# 19_EMMC_FLASH.net
KiCad netlist of a schematic drawn in Altium Designer
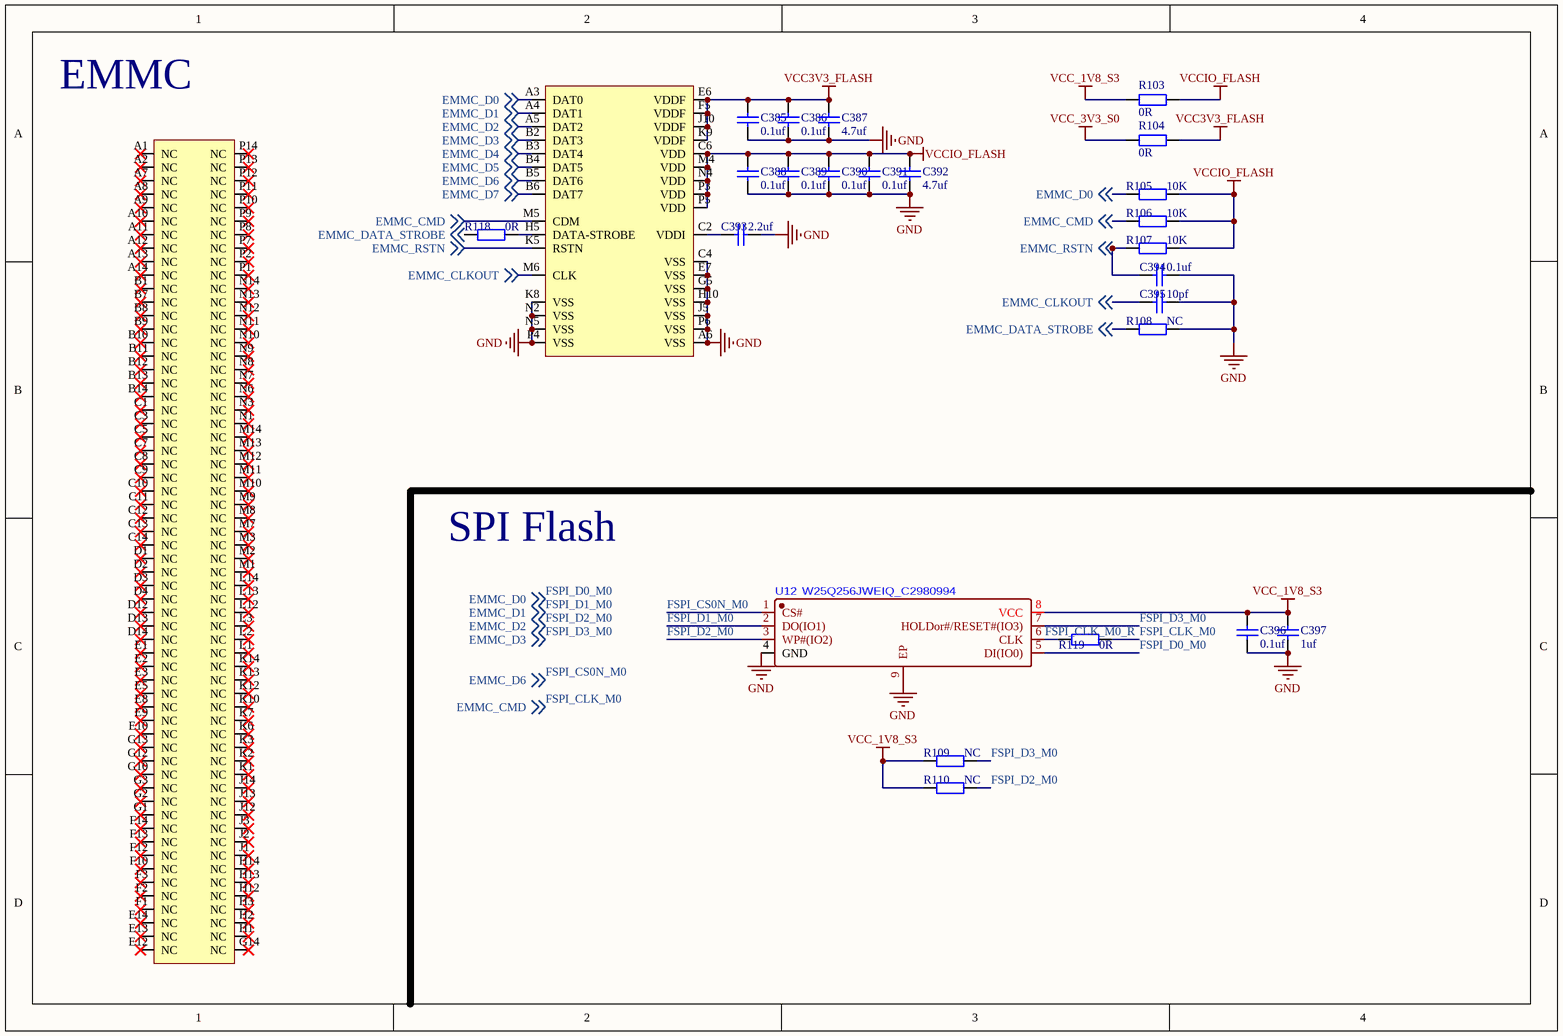
[diagram p0: 19.EMMC_FLASH.SchDoc]

(export (version "E")
  (design (tool "Eeschema 10.0.6"))
  (components
    (comp (ref "C385")
      (value "0.1uf")
      (footprint "0.PCB1:C0402_L")
      (description "贴片电容/MLCC电容")
      (libsource (lib "RK3588") (part "C"))
    )
    (comp (ref "C386")
      (value "0.1uf")
      (footprint "0.PCB1:C0402_L")
      (description "贴片电容/MLCC电容")
      (libsource (lib "RK3588") (part "C"))
    )
    (comp (ref "C387")
      (value "4.7uf")
      (footprint "0.PCB1:C0402_L")
      (description "贴片电容/MLCC电容")
      (libsource (lib "RK3588") (part "C"))
    )
    (comp (ref "C388")
      (value "0.1uf")
      (footprint "0.PCB1:C0402_L")
      (description "贴片电容/MLCC电容")
      (libsource (lib "RK3588") (part "C"))
    )
    (comp (ref "C389")
      (value "0.1uf")
      (footprint "0.PCB1:C0402_L")
      (description "贴片电容/MLCC电容")
      (libsource (lib "RK3588") (part "C"))
    )
    (comp (ref "C390")
      (value "0.1uf")
      (footprint "0.PCB1:C0402_L")
      (description "贴片电容/MLCC电容")
      (libsource (lib "RK3588") (part "C"))
    )
    (comp (ref "C391")
      (value "0.1uf")
      (footprint "0.PCB1:C0402_L")
      (description "贴片电容/MLCC电容")
      (libsource (lib "RK3588") (part "C"))
    )
    (comp (ref "C392")
      (value "4.7uf")
      (footprint "0.PCB1:C0402_L")
      (description "贴片电容/MLCC电容")
      (libsource (lib "RK3588") (part "C"))
    )
    (comp (ref "C393")
      (value "2.2uf")
      (footprint "0.PCB1:C0402_L")
      (description "贴片电容/MLCC电容")
      (libsource (lib "RK3588") (part "C"))
    )
    (comp (ref "C394")
      (value "0.1uf")
      (footprint "0.PCB1:C0402_L")
      (description "贴片电容/MLCC电容")
      (libsource (lib "RK3588") (part "C"))
    )
    (comp (ref "C395")
      (value "10pf")
      (footprint "0.PCB1:C0402_L")
      (description "贴片电容/MLCC电容")
      (libsource (lib "RK3588") (part "C"))
    )
    (comp (ref "C396")
      (value "0.1uf")
      (footprint "0.PCB1:C0201_L")
      (description "贴片电容/MLCC电容")
      (libsource (lib "RK3588") (part "C"))
    )
    (comp (ref "C397")
      (value "1uf")
      (footprint "0.PCB1:C0402_L")
      (description "贴片电容/MLCC电容")
      (libsource (lib "RK3588") (part "C"))
    )
    (comp (ref "R103")
      (value "0R")
      (footprint "0.PCB1:R0603_L")
      (description "贴片电阻")
      (libsource (lib "RK3588") (part "R"))
    )
    (comp (ref "R104")
      (value "0R")
      (footprint "0.PCB1:R0603_L")
      (description "贴片电阻")
      (libsource (lib "RK3588") (part "R"))
    )
    (comp (ref "R105")
      (value "10K")
      (footprint "0.PCB1:R0402_L")
      (description "贴片电阻")
      (libsource (lib "RK3588") (part "R"))
    )
    (comp (ref "R106")
      (value "10K")
      (footprint "0.PCB1:R0402_L")
      (description "贴片电阻")
      (libsource (lib "RK3588") (part "R"))
    )
    (comp (ref "R107")
      (value "10K")
      (footprint "0.PCB1:R0402_L")
      (description "贴片电阻")
      (libsource (lib "RK3588") (part "R"))
    )
    (comp (ref "R108")
      (value "NC")
      (footprint "0.PCB1:R0402_L")
      (description "贴片电阻")
      (libsource (lib "RK3588") (part "R"))
    )
    (comp (ref "R109")
      (value "NC")
      (footprint "0.PCB1:R0201_L")
      (description "贴片电阻")
      (libsource (lib "RK3588") (part "R"))
    )
    (comp (ref "R110")
      (value "NC")
      (footprint "0.PCB1:R0201_L")
      (description "贴片电阻")
      (libsource (lib "RK3588") (part "R"))
    )
    (comp (ref "R118")
      (value "0R")
      (footprint "0.PCB1:R0201_L")
      (description "贴片电阻")
      (libsource (lib "RK3588") (part "R"))
    )
    (comp (ref "R119")
      (value "0R")
      (footprint "0.PCB1:R0201_L")
      (description "贴片电阻")
      (libsource (lib "RK3588") (part "R"))
    )
    (comp (ref "U11")
      (value "KLMBG2JETD-B041")
      (footprint "0.PCB1:FBGA-153")
      (description "32GB EMMC5.1")
      (libsource (lib "RK3588") (part "KLMBG2JETD-B041"))
    )
    (comp (ref "U12")
      (value "W25Q256JWEIQ_C2980994")
      (footprint "0.PCB1:WSON-8_L8.0-W6.0-P1.27-TL-EP-1")
      (libsource (lib "RK3588") (part "W25Q256JWEIQ_C2980994"))
    )
  )
  (nets
    (net (code "1") (name "/FSPI_CLK_M0_R") (class "Default")
      (node (ref "R119") (pin "1") (pinfunction "1_1") (pintype "passive"))
      (node (ref "U12") (pin "6") (pinfunction "CLK_6") (pintype "passive"))
    )
    (net (code "2") (name "EMMC_CLKOUT") (class "Default")
      (node (ref "C395") (pin "2") (pinfunction "2_2") (pintype "passive"))
      (node (ref "U11") (pin "M6") (pinfunction "CLK_M6") (pintype "passive"))
    )
    (net (code "3") (name "EMMC_CMD") (class "Default")
      (node (ref "R106") (pin "2") (pinfunction "2_2") (pintype "passive"))
      (node (ref "R119") (pin "2") (pinfunction "2_2") (pintype "passive"))
      (node (ref "U11") (pin "M5") (pinfunction "CDM_M5") (pintype "passive"))
    )
    (net (code "4") (name "EMMC_D0") (class "Default")
      (node (ref "R105") (pin "2") (pinfunction "2_2") (pintype "passive"))
      (node (ref "U11") (pin "A3") (pinfunction "DAT0_A3") (pintype "passive"))
      (node (ref "U12") (pin "5") (pinfunction "DI(IO0)_5") (pintype "passive"))
    )
    (net (code "5") (name "EMMC_D1") (class "Default")
      (node (ref "U11") (pin "A4") (pinfunction "DAT1_A4") (pintype "passive"))
      (node (ref "U12") (pin "2") (pinfunction "DO(IO1)_2") (pintype "passive"))
    )
    (net (code "6") (name "EMMC_D2") (class "Default")
      (node (ref "R110") (pin "2") (pinfunction "2_2") (pintype "passive"))
      (node (ref "U11") (pin "A5") (pinfunction "DAT2_A5") (pintype "passive"))
      (node (ref "U12") (pin "3") (pinfunction "WP#(IO2)_3") (pintype "passive"))
    )
    (net (code "7") (name "EMMC_D3") (class "Default")
      (node (ref "R109") (pin "2") (pinfunction "2_2") (pintype "passive"))
      (node (ref "U11") (pin "B2") (pinfunction "DAT3_B2") (pintype "passive"))
      (node (ref "U12") (pin "7") (pinfunction "HOLDor#/RESET#(IO3)_7") (pintype "passive"))
    )
    (net (code "8") (name "EMMC_D4") (class "Default")
      (node (ref "U11") (pin "B3") (pinfunction "DAT4_B3") (pintype "passive"))
    )
    (net (code "9") (name "EMMC_D5") (class "Default")
      (node (ref "U11") (pin "B4") (pinfunction "DAT5_B4") (pintype "passive"))
    )
    (net (code "10") (name "EMMC_D6") (class "Default")
      (node (ref "U11") (pin "B5") (pinfunction "DAT6_B5") (pintype "passive"))
      (node (ref "U12") (pin "1") (pinfunction "CS#_1") (pintype "passive"))
    )
    (net (code "11") (name "EMMC_D7") (class "Default")
      (node (ref "U11") (pin "B6") (pinfunction "DAT7_B6") (pintype "passive"))
    )
    (net (code "12") (name "EMMC_DATA_STROBE") (class "Default")
      (node (ref "R108") (pin "2") (pinfunction "2_2") (pintype "passive"))
      (node (ref "R118") (pin "1") (pinfunction "1_1") (pintype "passive"))
    )
    (net (code "13") (name "EMMC_RSTN") (class "Default")
      (node (ref "C394") (pin "2") (pinfunction "2_2") (pintype "passive"))
      (node (ref "R107") (pin "2") (pinfunction "2_2") (pintype "passive"))
      (node (ref "U11") (pin "K5") (pinfunction "RSTN_K5") (pintype "passive"))
    )
    (net (code "14") (name "GND") (class "Default")
      (node (ref "C385") (pin "2") (pinfunction "2_2") (pintype "passive"))
      (node (ref "C386") (pin "2") (pinfunction "2_2") (pintype "passive"))
      (node (ref "C387") (pin "2") (pinfunction "2_2") (pintype "passive"))
      (node (ref "C388") (pin "2") (pinfunction "2_2") (pintype "passive"))
      (node (ref "C389") (pin "2") (pinfunction "2_2") (pintype "passive"))
      (node (ref "C390") (pin "2") (pinfunction "2_2") (pintype "passive"))
      (node (ref "C391") (pin "2") (pinfunction "2_2") (pintype "passive"))
      (node (ref "C392") (pin "2") (pinfunction "2_2") (pintype "passive"))
      (node (ref "C393") (pin "1") (pinfunction "1_1") (pintype "passive"))
      (node (ref "C394") (pin "1") (pinfunction "1_1") (pintype "passive"))
      (node (ref "C395") (pin "1") (pinfunction "1_1") (pintype "passive"))
      (node (ref "C396") (pin "1") (pinfunction "1_1") (pintype "passive"))
      (node (ref "C397") (pin "1") (pinfunction "1_1") (pintype "passive"))
      (node (ref "R108") (pin "1") (pinfunction "1_1") (pintype "passive"))
      (node (ref "U11") (pin "A6") (pinfunction "VSS_A6") (pintype "passive"))
      (node (ref "U11") (pin "C4") (pinfunction "VSS_C4") (pintype "passive"))
      (node (ref "U11") (pin "E7") (pinfunction "VSS_E7") (pintype "passive"))
      (node (ref "U11") (pin "G5") (pinfunction "VSS_G5") (pintype "passive"))
      (node (ref "U11") (pin "H10") (pinfunction "VSS_H10") (pintype "passive"))
      (node (ref "U11") (pin "J5") (pinfunction "VSS_J5") (pintype "passive"))
      (node (ref "U11") (pin "K8") (pinfunction "VSS_K8") (pintype "passive"))
      (node (ref "U11") (pin "N2") (pinfunction "VSS_N2") (pintype "passive"))
      (node (ref "U11") (pin "N5") (pinfunction "VSS_N5") (pintype "passive"))
      (node (ref "U11") (pin "P4") (pinfunction "VSS_P4") (pintype "passive"))
      (node (ref "U11") (pin "P6") (pinfunction "VSS_P6") (pintype "passive"))
      (node (ref "U12") (pin "4") (pinfunction "GND_4") (pintype "passive"))
      (node (ref "U12") (pin "9") (pinfunction "EP_9") (pintype "passive"))
    )
    (net (code "15") (name "Net-(U11A-DATA-STROBE)") (class "Default")
      (node (ref "R118") (pin "2") (pinfunction "2_2") (pintype "passive"))
      (node (ref "U11") (pin "H5") (pinfunction "DATA-STROBE_H5") (pintype "passive"))
    )
    (net (code "16") (name "Net-(U11A-VDDI)") (class "Default")
      (node (ref "C393") (pin "2") (pinfunction "2_2") (pintype "passive"))
      (node (ref "U11") (pin "C2") (pinfunction "VDDI_C2") (pintype "passive"))
    )
    (net (code "17") (name "VCC3V3_FLASH") (class "Default")
      (node (ref "C385") (pin "1") (pinfunction "1_1") (pintype "passive"))
      (node (ref "C386") (pin "1") (pinfunction "1_1") (pintype "passive"))
      (node (ref "C387") (pin "1") (pinfunction "1_1") (pintype "passive"))
      (node (ref "R104") (pin "2") (pinfunction "2_2") (pintype "passive"))
      (node (ref "U11") (pin "E6") (pinfunction "VDDF_E6") (pintype "passive"))
      (node (ref "U11") (pin "F5") (pinfunction "VDDF_F5") (pintype "passive"))
      (node (ref "U11") (pin "J10") (pinfunction "VDDF_J10") (pintype "passive"))
      (node (ref "U11") (pin "K9") (pinfunction "VDDF_K9") (pintype "passive"))
    )
    (net (code "18") (name "VCCIO_FLASH") (class "Default")
      (node (ref "C388") (pin "1") (pinfunction "1_1") (pintype "passive"))
      (node (ref "C389") (pin "1") (pinfunction "1_1") (pintype "passive"))
      (node (ref "C390") (pin "1") (pinfunction "1_1") (pintype "passive"))
      (node (ref "C391") (pin "1") (pinfunction "1_1") (pintype "passive"))
      (node (ref "C392") (pin "1") (pinfunction "1_1") (pintype "passive"))
      (node (ref "R103") (pin "2") (pinfunction "2_2") (pintype "passive"))
      (node (ref "R105") (pin "1") (pinfunction "1_1") (pintype "passive"))
      (node (ref "R106") (pin "1") (pinfunction "1_1") (pintype "passive"))
      (node (ref "R107") (pin "1") (pinfunction "1_1") (pintype "passive"))
      (node (ref "U11") (pin "C6") (pinfunction "VDD_C6") (pintype "passive"))
      (node (ref "U11") (pin "M4") (pinfunction "VDD_M4") (pintype "passive"))
      (node (ref "U11") (pin "N4") (pinfunction "VDD_N4") (pintype "passive"))
      (node (ref "U11") (pin "P3") (pinfunction "VDD_P3") (pintype "passive"))
      (node (ref "U11") (pin "P5") (pinfunction "VDD_P5") (pintype "passive"))
    )
    (net (code "19") (name "VCC_1V8_S3") (class "Default")
      (node (ref "C396") (pin "2") (pinfunction "2_2") (pintype "passive"))
      (node (ref "C397") (pin "2") (pinfunction "2_2") (pintype "passive"))
      (node (ref "R103") (pin "1") (pinfunction "1_1") (pintype "passive"))
      (node (ref "R109") (pin "1") (pinfunction "1_1") (pintype "passive"))
      (node (ref "R110") (pin "1") (pinfunction "1_1") (pintype "passive"))
      (node (ref "U12") (pin "8") (pinfunction "VCC_8") (pintype "passive"))
    )
    (net (code "20") (name "VCC_3V3_S0") (class "Default")
      (node (ref "R104") (pin "1") (pinfunction "1_1") (pintype "passive"))
    )
    (net (code "21") (name "unconnected-(U11B-NC-PadA1)") (class "Default")
      (node (ref "U11") (pin "A1") (pinfunction "NC_A1") (pintype "passive+no_connect"))
    )
    (net (code "22") (name "unconnected-(U11B-NC-PadA2)") (class "Default")
      (node (ref "U11") (pin "A2") (pinfunction "NC_A2") (pintype "passive+no_connect"))
    )
    (net (code "23") (name "unconnected-(U11B-NC-PadA7)") (class "Default")
      (node (ref "U11") (pin "A7") (pinfunction "NC_A7") (pintype "passive+no_connect"))
    )
    (net (code "24") (name "unconnected-(U11B-NC-PadA8)") (class "Default")
      (node (ref "U11") (pin "A8") (pinfunction "NC_A8") (pintype "passive+no_connect"))
    )
    (net (code "25") (name "unconnected-(U11B-NC-PadA9)") (class "Default")
      (node (ref "U11") (pin "A9") (pinfunction "NC_A9") (pintype "passive+no_connect"))
    )
    (net (code "26") (name "unconnected-(U11B-NC-PadA10)") (class "Default")
      (node (ref "U11") (pin "A10") (pinfunction "NC_A10") (pintype "passive+no_connect"))
    )
    (net (code "27") (name "unconnected-(U11B-NC-PadA11)") (class "Default")
      (node (ref "U11") (pin "A11") (pinfunction "NC_A11") (pintype "passive+no_connect"))
    )
    (net (code "28") (name "unconnected-(U11B-NC-PadA12)") (class "Default")
      (node (ref "U11") (pin "A12") (pinfunction "NC_A12") (pintype "passive+no_connect"))
    )
    (net (code "29") (name "unconnected-(U11B-NC-PadA13)") (class "Default")
      (node (ref "U11") (pin "A13") (pinfunction "NC_A13") (pintype "passive+no_connect"))
    )
    (net (code "30") (name "unconnected-(U11B-NC-PadA14)") (class "Default")
      (node (ref "U11") (pin "A14") (pinfunction "NC_A14") (pintype "passive+no_connect"))
    )
    (net (code "31") (name "unconnected-(U11B-NC-PadB1)") (class "Default")
      (node (ref "U11") (pin "B1") (pinfunction "NC_B1") (pintype "passive+no_connect"))
    )
    (net (code "32") (name "unconnected-(U11B-NC-PadB7)") (class "Default")
      (node (ref "U11") (pin "B7") (pinfunction "NC_B7") (pintype "passive+no_connect"))
    )
    (net (code "33") (name "unconnected-(U11B-NC-PadB8)") (class "Default")
      (node (ref "U11") (pin "B8") (pinfunction "NC_B8") (pintype "passive+no_connect"))
    )
    (net (code "34") (name "unconnected-(U11B-NC-PadB9)") (class "Default")
      (node (ref "U11") (pin "B9") (pinfunction "NC_B9") (pintype "passive+no_connect"))
    )
    (net (code "35") (name "unconnected-(U11B-NC-PadB10)") (class "Default")
      (node (ref "U11") (pin "B10") (pinfunction "NC_B10") (pintype "passive+no_connect"))
    )
    (net (code "36") (name "unconnected-(U11B-NC-PadB11)") (class "Default")
      (node (ref "U11") (pin "B11") (pinfunction "NC_B11") (pintype "passive+no_connect"))
    )
    (net (code "37") (name "unconnected-(U11B-NC-PadB12)") (class "Default")
      (node (ref "U11") (pin "B12") (pinfunction "NC_B12") (pintype "passive+no_connect"))
    )
    (net (code "38") (name "unconnected-(U11B-NC-PadB13)") (class "Default")
      (node (ref "U11") (pin "B13") (pinfunction "NC_B13") (pintype "passive+no_connect"))
    )
    (net (code "39") (name "unconnected-(U11B-NC-PadB14)") (class "Default")
      (node (ref "U11") (pin "B14") (pinfunction "NC_B14") (pintype "passive+no_connect"))
    )
    (net (code "40") (name "unconnected-(U11B-NC-PadC1)") (class "Default")
      (node (ref "U11") (pin "C1") (pinfunction "NC_C1") (pintype "passive+no_connect"))
    )
    (net (code "41") (name "unconnected-(U11B-NC-PadC3)") (class "Default")
      (node (ref "U11") (pin "C3") (pinfunction "NC_C3") (pintype "passive+no_connect"))
    )
    (net (code "42") (name "unconnected-(U11B-NC-PadC5)") (class "Default")
      (node (ref "U11") (pin "C5") (pinfunction "NC_C5") (pintype "passive+no_connect"))
    )
    (net (code "43") (name "unconnected-(U11B-NC-PadC7)") (class "Default")
      (node (ref "U11") (pin "C7") (pinfunction "NC_C7") (pintype "passive+no_connect"))
    )
    (net (code "44") (name "unconnected-(U11B-NC-PadC8)") (class "Default")
      (node (ref "U11") (pin "C8") (pinfunction "NC_C8") (pintype "passive+no_connect"))
    )
    (net (code "45") (name "unconnected-(U11B-NC-PadC9)") (class "Default")
      (node (ref "U11") (pin "C9") (pinfunction "NC_C9") (pintype "passive+no_connect"))
    )
    (net (code "46") (name "unconnected-(U11B-NC-PadC10)") (class "Default")
      (node (ref "U11") (pin "C10") (pinfunction "NC_C10") (pintype "passive+no_connect"))
    )
    (net (code "47") (name "unconnected-(U11B-NC-PadC11)") (class "Default")
      (node (ref "U11") (pin "C11") (pinfunction "NC_C11") (pintype "passive+no_connect"))
    )
    (net (code "48") (name "unconnected-(U11B-NC-PadC12)") (class "Default")
      (node (ref "U11") (pin "C12") (pinfunction "NC_C12") (pintype "passive+no_connect"))
    )
    (net (code "49") (name "unconnected-(U11B-NC-PadC13)") (class "Default")
      (node (ref "U11") (pin "C13") (pinfunction "NC_C13") (pintype "passive+no_connect"))
    )
    (net (code "50") (name "unconnected-(U11B-NC-PadC14)") (class "Default")
      (node (ref "U11") (pin "C14") (pinfunction "NC_C14") (pintype "passive+no_connect"))
    )
    (net (code "51") (name "unconnected-(U11B-NC-PadD1)") (class "Default")
      (node (ref "U11") (pin "D1") (pinfunction "NC_D1") (pintype "passive+no_connect"))
    )
    (net (code "52") (name "unconnected-(U11B-NC-PadD2)") (class "Default")
      (node (ref "U11") (pin "D2") (pinfunction "NC_D2") (pintype "passive+no_connect"))
    )
    (net (code "53") (name "unconnected-(U11B-NC-PadD3)") (class "Default")
      (node (ref "U11") (pin "D3") (pinfunction "NC_D3") (pintype "passive+no_connect"))
    )
    (net (code "54") (name "unconnected-(U11B-NC-PadD4)") (class "Default")
      (node (ref "U11") (pin "D4") (pinfunction "NC_D4") (pintype "passive+no_connect"))
    )
    (net (code "55") (name "unconnected-(U11B-NC-PadD12)") (class "Default")
      (node (ref "U11") (pin "D12") (pinfunction "NC_D12") (pintype "passive+no_connect"))
    )
    (net (code "56") (name "unconnected-(U11B-NC-PadD13)") (class "Default")
      (node (ref "U11") (pin "D13") (pinfunction "NC_D13") (pintype "passive+no_connect"))
    )
    (net (code "57") (name "unconnected-(U11B-NC-PadD14)") (class "Default")
      (node (ref "U11") (pin "D14") (pinfunction "NC_D14") (pintype "passive+no_connect"))
    )
    (net (code "58") (name "unconnected-(U11B-NC-PadE1)") (class "Default")
      (node (ref "U11") (pin "E1") (pinfunction "NC_E1") (pintype "passive+no_connect"))
    )
    (net (code "59") (name "unconnected-(U11B-NC-PadE2)") (class "Default")
      (node (ref "U11") (pin "E2") (pinfunction "NC_E2") (pintype "passive+no_connect"))
    )
    (net (code "60") (name "unconnected-(U11B-NC-PadE3)") (class "Default")
      (node (ref "U11") (pin "E3") (pinfunction "NC_E3") (pintype "passive+no_connect"))
    )
    (net (code "61") (name "unconnected-(U11B-NC-PadE5)") (class "Default")
      (node (ref "U11") (pin "E5") (pinfunction "NC_E5") (pintype "passive+no_connect"))
    )
    (net (code "62") (name "unconnected-(U11B-NC-PadE8)") (class "Default")
      (node (ref "U11") (pin "E8") (pinfunction "NC_E8") (pintype "passive+no_connect"))
    )
    (net (code "63") (name "unconnected-(U11B-NC-PadE9)") (class "Default")
      (node (ref "U11") (pin "E9") (pinfunction "NC_E9") (pintype "passive+no_connect"))
    )
    (net (code "64") (name "unconnected-(U11B-NC-PadE10)") (class "Default")
      (node (ref "U11") (pin "E10") (pinfunction "NC_E10") (pintype "passive+no_connect"))
    )
    (net (code "65") (name "unconnected-(U11B-NC-PadE12)") (class "Default")
      (node (ref "U11") (pin "E12") (pinfunction "NC_E12") (pintype "passive+no_connect"))
    )
    (net (code "66") (name "unconnected-(U11B-NC-PadE13)") (class "Default")
      (node (ref "U11") (pin "E13") (pinfunction "NC_E13") (pintype "passive+no_connect"))
    )
    (net (code "67") (name "unconnected-(U11B-NC-PadE14)") (class "Default")
      (node (ref "U11") (pin "E14") (pinfunction "NC_E14") (pintype "passive+no_connect"))
    )
    (net (code "68") (name "unconnected-(U11B-NC-PadF1)") (class "Default")
      (node (ref "U11") (pin "F1") (pinfunction "NC_F1") (pintype "passive+no_connect"))
    )
    (net (code "69") (name "unconnected-(U11B-NC-PadF2)") (class "Default")
      (node (ref "U11") (pin "F2") (pinfunction "NC_F2") (pintype "passive+no_connect"))
    )
    (net (code "70") (name "unconnected-(U11B-NC-PadF3)") (class "Default")
      (node (ref "U11") (pin "F3") (pinfunction "NC_F3") (pintype "passive+no_connect"))
    )
    (net (code "71") (name "unconnected-(U11B-NC-PadF10)") (class "Default")
      (node (ref "U11") (pin "F10") (pinfunction "NC_F10") (pintype "passive+no_connect"))
    )
    (net (code "72") (name "unconnected-(U11B-NC-PadF12)") (class "Default")
      (node (ref "U11") (pin "F12") (pinfunction "NC_F12") (pintype "passive+no_connect"))
    )
    (net (code "73") (name "unconnected-(U11B-NC-PadF13)") (class "Default")
      (node (ref "U11") (pin "F13") (pinfunction "NC_F13") (pintype "passive+no_connect"))
    )
    (net (code "74") (name "unconnected-(U11B-NC-PadF14)") (class "Default")
      (node (ref "U11") (pin "F14") (pinfunction "NC_F14") (pintype "passive+no_connect"))
    )
    (net (code "75") (name "unconnected-(U11B-NC-PadG1)") (class "Default")
      (node (ref "U11") (pin "G1") (pinfunction "NC_G1") (pintype "passive+no_connect"))
    )
    (net (code "76") (name "unconnected-(U11B-NC-PadG2)") (class "Default")
      (node (ref "U11") (pin "G2") (pinfunction "NC_G2") (pintype "passive+no_connect"))
    )
    (net (code "77") (name "unconnected-(U11B-NC-PadG3)") (class "Default")
      (node (ref "U11") (pin "G3") (pinfunction "NC_G3") (pintype "passive+no_connect"))
    )
    (net (code "78") (name "unconnected-(U11B-NC-PadG10)") (class "Default")
      (node (ref "U11") (pin "G10") (pinfunction "NC_G10") (pintype "passive+no_connect"))
    )
    (net (code "79") (name "unconnected-(U11B-NC-PadG12)") (class "Default")
      (node (ref "U11") (pin "G12") (pinfunction "NC_G12") (pintype "passive+no_connect"))
    )
    (net (code "80") (name "unconnected-(U11B-NC-PadG13)") (class "Default")
      (node (ref "U11") (pin "G13") (pinfunction "NC_G13") (pintype "passive+no_connect"))
    )
    (net (code "81") (name "unconnected-(U11B-NC-PadG14)") (class "Default")
      (node (ref "U11") (pin "G14") (pinfunction "NC_G14") (pintype "passive+no_connect"))
    )
    (net (code "82") (name "unconnected-(U11B-NC-PadH1)") (class "Default")
      (node (ref "U11") (pin "H1") (pinfunction "NC_H1") (pintype "passive+no_connect"))
    )
    (net (code "83") (name "unconnected-(U11B-NC-PadH2)") (class "Default")
      (node (ref "U11") (pin "H2") (pinfunction "NC_H2") (pintype "passive+no_connect"))
    )
    (net (code "84") (name "unconnected-(U11B-NC-PadH3)") (class "Default")
      (node (ref "U11") (pin "H3") (pinfunction "NC_H3") (pintype "passive+no_connect"))
    )
    (net (code "85") (name "unconnected-(U11B-NC-PadH12)") (class "Default")
      (node (ref "U11") (pin "H12") (pinfunction "NC_H12") (pintype "passive+no_connect"))
    )
    (net (code "86") (name "unconnected-(U11B-NC-PadH13)") (class "Default")
      (node (ref "U11") (pin "H13") (pinfunction "NC_H13") (pintype "passive+no_connect"))
    )
    (net (code "87") (name "unconnected-(U11B-NC-PadH14)") (class "Default")
      (node (ref "U11") (pin "H14") (pinfunction "NC_H14") (pintype "passive+no_connect"))
    )
    (net (code "88") (name "unconnected-(U11B-NC-PadJ1)") (class "Default")
      (node (ref "U11") (pin "J1") (pinfunction "NC_J1") (pintype "passive+no_connect"))
    )
    (net (code "89") (name "unconnected-(U11B-NC-PadJ2)") (class "Default")
      (node (ref "U11") (pin "J2") (pinfunction "NC_J2") (pintype "passive+no_connect"))
    )
    (net (code "90") (name "unconnected-(U11B-NC-PadJ3)") (class "Default")
      (node (ref "U11") (pin "J3") (pinfunction "NC_J3") (pintype "passive+no_connect"))
    )
    (net (code "91") (name "unconnected-(U11B-NC-PadJ12)") (class "Default")
      (node (ref "U11") (pin "J12") (pinfunction "NC_J12") (pintype "passive+no_connect"))
    )
    (net (code "92") (name "unconnected-(U11B-NC-PadJ13)") (class "Default")
      (node (ref "U11") (pin "J13") (pinfunction "NC_J13") (pintype "passive+no_connect"))
    )
    (net (code "93") (name "unconnected-(U11B-NC-PadJ14)") (class "Default")
      (node (ref "U11") (pin "J14") (pinfunction "NC_J14") (pintype "passive+no_connect"))
    )
    (net (code "94") (name "unconnected-(U11B-NC-PadK1)") (class "Default")
      (node (ref "U11") (pin "K1") (pinfunction "NC_K1") (pintype "passive+no_connect"))
    )
    (net (code "95") (name "unconnected-(U11B-NC-PadK2)") (class "Default")
      (node (ref "U11") (pin "K2") (pinfunction "NC_K2") (pintype "passive+no_connect"))
    )
    (net (code "96") (name "unconnected-(U11B-NC-PadK3)") (class "Default")
      (node (ref "U11") (pin "K3") (pinfunction "NC_K3") (pintype "passive+no_connect"))
    )
    (net (code "97") (name "unconnected-(U11B-NC-PadK6)") (class "Default")
      (node (ref "U11") (pin "K6") (pinfunction "NC_K6") (pintype "passive+no_connect"))
    )
    (net (code "98") (name "unconnected-(U11B-NC-PadK7)") (class "Default")
      (node (ref "U11") (pin "K7") (pinfunction "NC_K7") (pintype "passive+no_connect"))
    )
    (net (code "99") (name "unconnected-(U11B-NC-PadK10)") (class "Default")
      (node (ref "U11") (pin "K10") (pinfunction "NC_K10") (pintype "passive+no_connect"))
    )
    (net (code "100") (name "unconnected-(U11B-NC-PadK12)") (class "Default")
      (node (ref "U11") (pin "K12") (pinfunction "NC_K12") (pintype "passive+no_connect"))
    )
    (net (code "101") (name "unconnected-(U11B-NC-PadK13)") (class "Default")
      (node (ref "U11") (pin "K13") (pinfunction "NC_K13") (pintype "passive+no_connect"))
    )
    (net (code "102") (name "unconnected-(U11B-NC-PadK14)") (class "Default")
      (node (ref "U11") (pin "K14") (pinfunction "NC_K14") (pintype "passive+no_connect"))
    )
    (net (code "103") (name "unconnected-(U11B-NC-PadL1)") (class "Default")
      (node (ref "U11") (pin "L1") (pinfunction "NC_L1") (pintype "passive+no_connect"))
    )
    (net (code "104") (name "unconnected-(U11B-NC-PadL2)") (class "Default")
      (node (ref "U11") (pin "L2") (pinfunction "NC_L2") (pintype "passive+no_connect"))
    )
    (net (code "105") (name "unconnected-(U11B-NC-PadL3)") (class "Default")
      (node (ref "U11") (pin "L3") (pinfunction "NC_L3") (pintype "passive+no_connect"))
    )
    (net (code "106") (name "unconnected-(U11B-NC-PadL12)") (class "Default")
      (node (ref "U11") (pin "L12") (pinfunction "NC_L12") (pintype "passive+no_connect"))
    )
    (net (code "107") (name "unconnected-(U11B-NC-PadL13)") (class "Default")
      (node (ref "U11") (pin "L13") (pinfunction "NC_L13") (pintype "passive+no_connect"))
    )
    (net (code "108") (name "unconnected-(U11B-NC-PadL14)") (class "Default")
      (node (ref "U11") (pin "L14") (pinfunction "NC_L14") (pintype "passive+no_connect"))
    )
    (net (code "109") (name "unconnected-(U11B-NC-PadM1)") (class "Default")
      (node (ref "U11") (pin "M1") (pinfunction "NC_M1") (pintype "passive+no_connect"))
    )
    (net (code "110") (name "unconnected-(U11B-NC-PadM2)") (class "Default")
      (node (ref "U11") (pin "M2") (pinfunction "NC_M2") (pintype "passive+no_connect"))
    )
    (net (code "111") (name "unconnected-(U11B-NC-PadM3)") (class "Default")
      (node (ref "U11") (pin "M3") (pinfunction "NC_M3") (pintype "passive+no_connect"))
    )
    (net (code "112") (name "unconnected-(U11B-NC-PadM7)") (class "Default")
      (node (ref "U11") (pin "M7") (pinfunction "NC_M7") (pintype "passive+no_connect"))
    )
    (net (code "113") (name "unconnected-(U11B-NC-PadM8)") (class "Default")
      (node (ref "U11") (pin "M8") (pinfunction "NC_M8") (pintype "passive+no_connect"))
    )
    (net (code "114") (name "unconnected-(U11B-NC-PadM9)") (class "Default")
      (node (ref "U11") (pin "M9") (pinfunction "NC_M9") (pintype "passive+no_connect"))
    )
    (net (code "115") (name "unconnected-(U11B-NC-PadM10)") (class "Default")
      (node (ref "U11") (pin "M10") (pinfunction "NC_M10") (pintype "passive+no_connect"))
    )
    (net (code "116") (name "unconnected-(U11B-NC-PadM11)") (class "Default")
      (node (ref "U11") (pin "M11") (pinfunction "NC_M11") (pintype "passive+no_connect"))
    )
    (net (code "117") (name "unconnected-(U11B-NC-PadM12)") (class "Default")
      (node (ref "U11") (pin "M12") (pinfunction "NC_M12") (pintype "passive+no_connect"))
    )
    (net (code "118") (name "unconnected-(U11B-NC-PadM13)") (class "Default")
      (node (ref "U11") (pin "M13") (pinfunction "NC_M13") (pintype "passive+no_connect"))
    )
    (net (code "119") (name "unconnected-(U11B-NC-PadM14)") (class "Default")
      (node (ref "U11") (pin "M14") (pinfunction "NC_M14") (pintype "passive+no_connect"))
    )
    (net (code "120") (name "unconnected-(U11B-NC-PadN1)") (class "Default")
      (node (ref "U11") (pin "N1") (pinfunction "NC_N1") (pintype "passive+no_connect"))
    )
    (net (code "121") (name "unconnected-(U11B-NC-PadN3)") (class "Default")
      (node (ref "U11") (pin "N3") (pinfunction "NC_N3") (pintype "passive+no_connect"))
    )
    (net (code "122") (name "unconnected-(U11B-NC-PadN6)") (class "Default")
      (node (ref "U11") (pin "N6") (pinfunction "NC_N6") (pintype "passive+no_connect"))
    )
    (net (code "123") (name "unconnected-(U11B-NC-PadN7)") (class "Default")
      (node (ref "U11") (pin "N7") (pinfunction "NC_N7") (pintype "passive+no_connect"))
    )
    (net (code "124") (name "unconnected-(U11B-NC-PadN8)") (class "Default")
      (node (ref "U11") (pin "N8") (pinfunction "NC_N8") (pintype "passive+no_connect"))
    )
    (net (code "125") (name "unconnected-(U11B-NC-PadN9)") (class "Default")
      (node (ref "U11") (pin "N9") (pinfunction "NC_N9") (pintype "passive+no_connect"))
    )
    (net (code "126") (name "unconnected-(U11B-NC-PadN10)") (class "Default")
      (node (ref "U11") (pin "N10") (pinfunction "NC_N10") (pintype "passive+no_connect"))
    )
    (net (code "127") (name "unconnected-(U11B-NC-PadN11)") (class "Default")
      (node (ref "U11") (pin "N11") (pinfunction "NC_N11") (pintype "passive+no_connect"))
    )
    (net (code "128") (name "unconnected-(U11B-NC-PadN12)") (class "Default")
      (node (ref "U11") (pin "N12") (pinfunction "NC_N12") (pintype "passive+no_connect"))
    )
    (net (code "129") (name "unconnected-(U11B-NC-PadN13)") (class "Default")
      (node (ref "U11") (pin "N13") (pinfunction "NC_N13") (pintype "passive+no_connect"))
    )
    (net (code "130") (name "unconnected-(U11B-NC-PadN14)") (class "Default")
      (node (ref "U11") (pin "N14") (pinfunction "NC_N14") (pintype "passive+no_connect"))
    )
    (net (code "131") (name "unconnected-(U11B-NC-PadP1)") (class "Default")
      (node (ref "U11") (pin "P1") (pinfunction "NC_P1") (pintype "passive+no_connect"))
    )
    (net (code "132") (name "unconnected-(U11B-NC-PadP2)") (class "Default")
      (node (ref "U11") (pin "P2") (pinfunction "NC_P2") (pintype "passive+no_connect"))
    )
    (net (code "133") (name "unconnected-(U11B-NC-PadP7)") (class "Default")
      (node (ref "U11") (pin "P7") (pinfunction "NC_P7") (pintype "passive+no_connect"))
    )
    (net (code "134") (name "unconnected-(U11B-NC-PadP8)") (class "Default")
      (node (ref "U11") (pin "P8") (pinfunction "NC_P8") (pintype "passive+no_connect"))
    )
    (net (code "135") (name "unconnected-(U11B-NC-PadP9)") (class "Default")
      (node (ref "U11") (pin "P9") (pinfunction "NC_P9") (pintype "passive+no_connect"))
    )
    (net (code "136") (name "unconnected-(U11B-NC-PadP10)") (class "Default")
      (node (ref "U11") (pin "P10") (pinfunction "NC_P10") (pintype "passive+no_connect"))
    )
    (net (code "137") (name "unconnected-(U11B-NC-PadP11)") (class "Default")
      (node (ref "U11") (pin "P11") (pinfunction "NC_P11") (pintype "passive+no_connect"))
    )
    (net (code "138") (name "unconnected-(U11B-NC-PadP12)") (class "Default")
      (node (ref "U11") (pin "P12") (pinfunction "NC_P12") (pintype "passive+no_connect"))
    )
    (net (code "139") (name "unconnected-(U11B-NC-PadP13)") (class "Default")
      (node (ref "U11") (pin "P13") (pinfunction "NC_P13") (pintype "passive+no_connect"))
    )
    (net (code "140") (name "unconnected-(U11B-NC-PadP14)") (class "Default")
      (node (ref "U11") (pin "P14") (pinfunction "NC_P14") (pintype "passive+no_connect"))
    )
  )
)
